# CY8C4125AZI-S433.net
KiCad netlist of a schematic drawn in Altium Designer
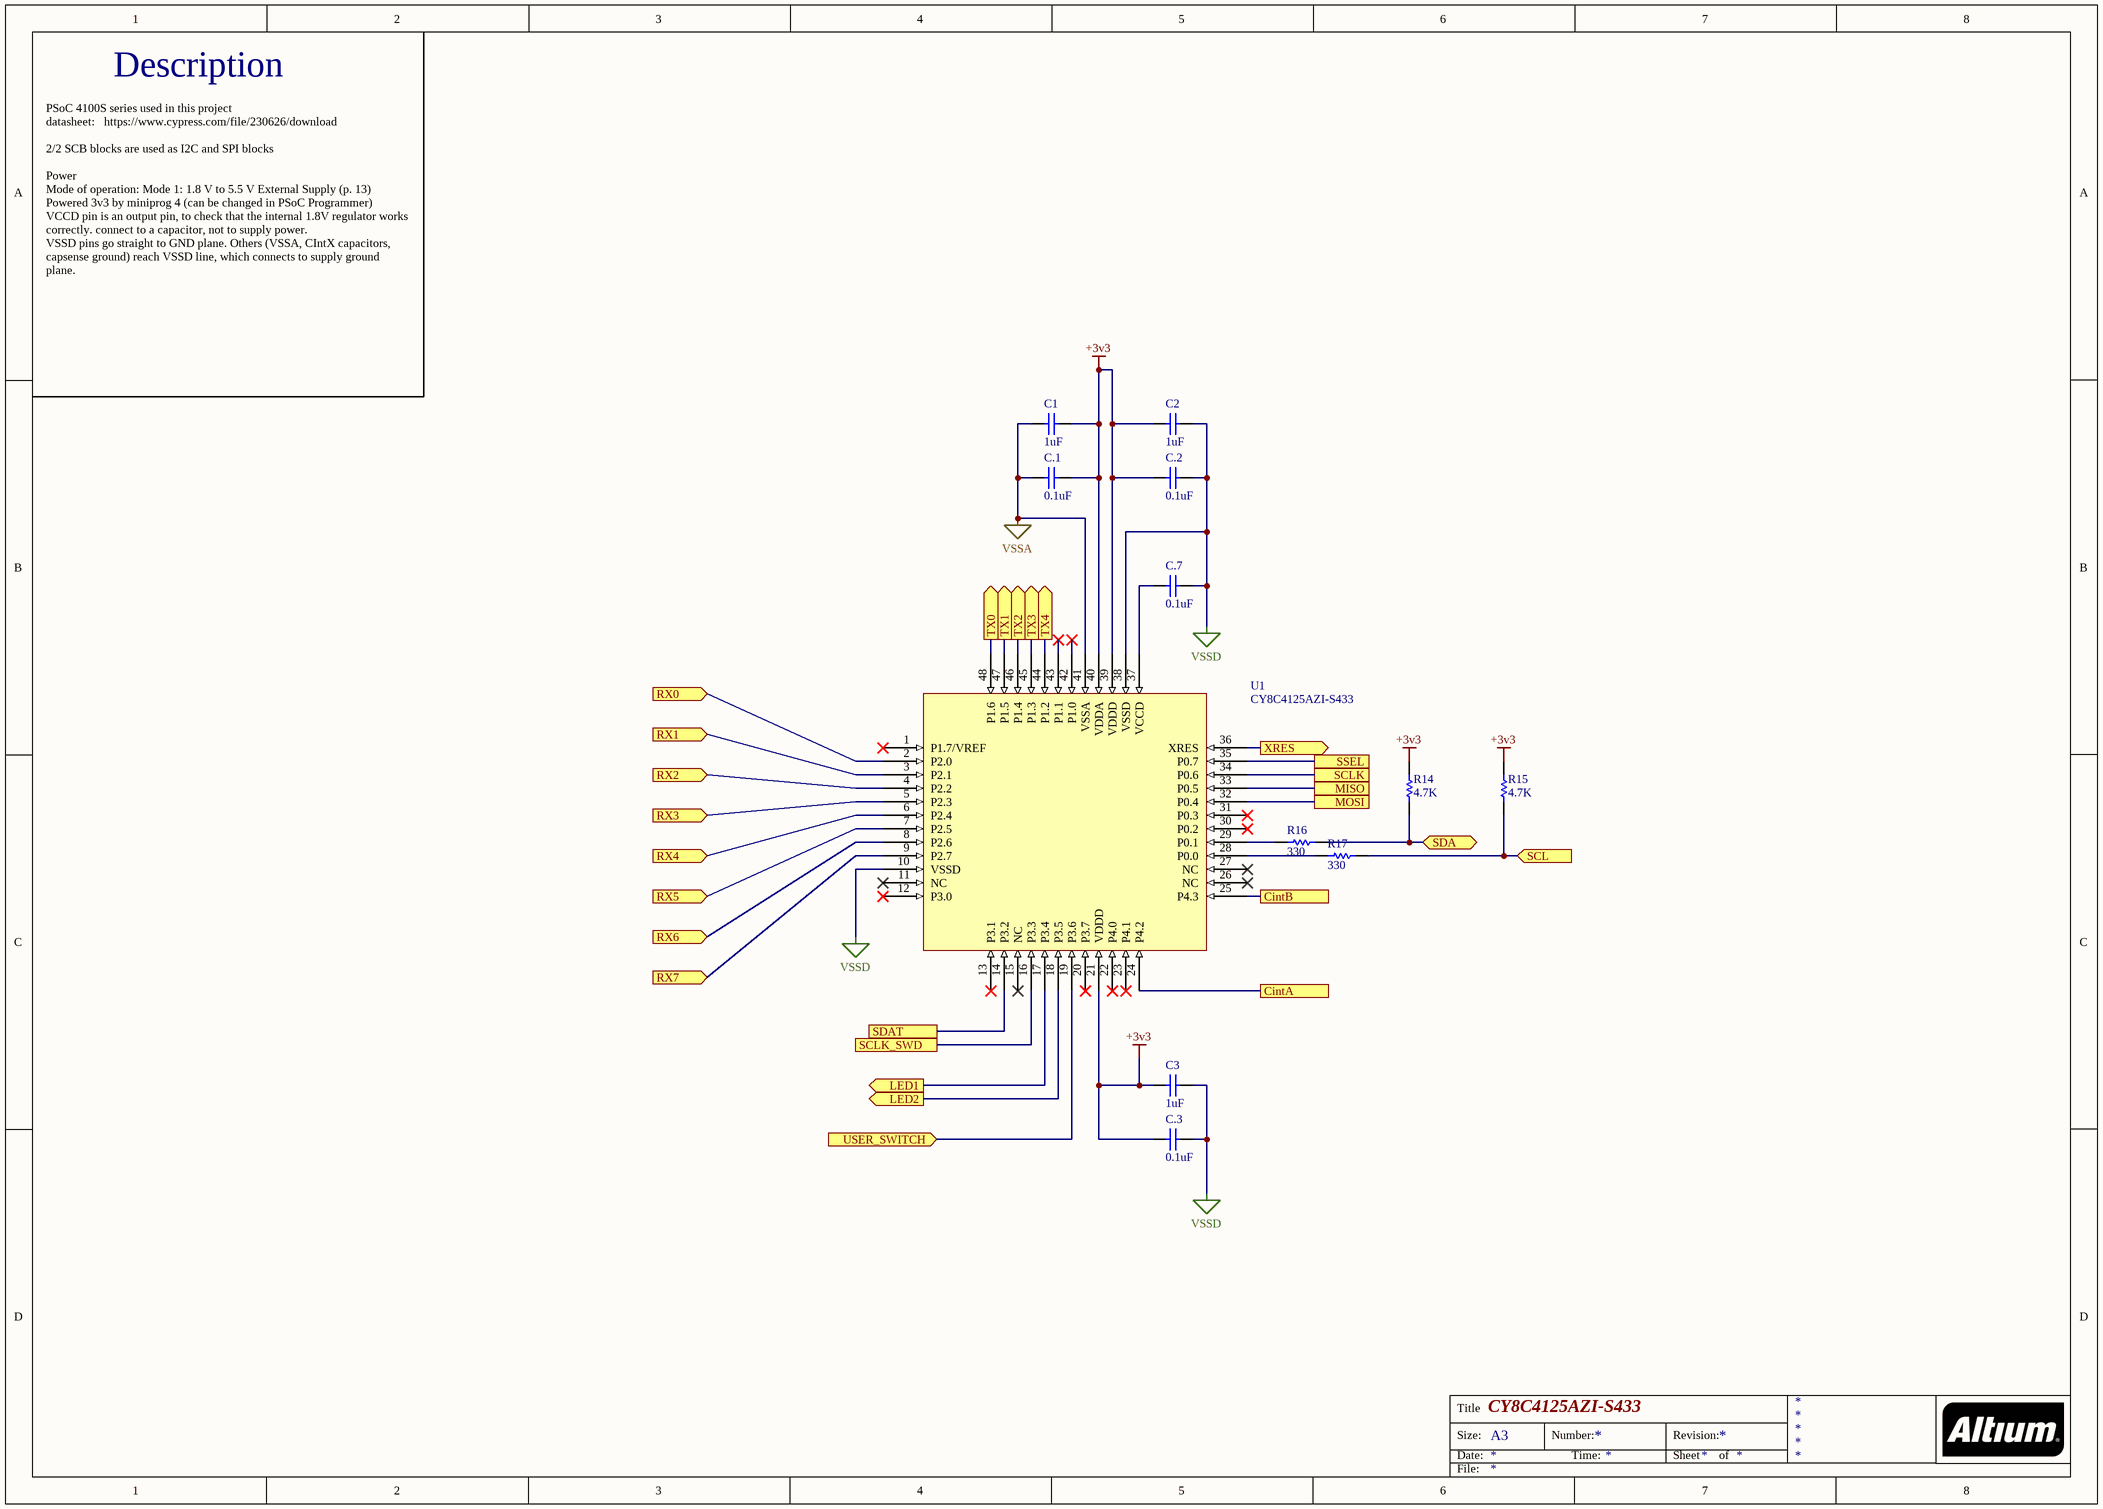
[diagram p0: CY8C4125AZI-S433.SchDoc]

(export (version "E")
  (design (tool "Eeschema 10.0.6"))
  (components
    (comp (ref "C.1")
      (value "0.1uF")
      (footprint "CAPC0603(1608)100_N")
      (description "CAP 0.1 uF 50V ±20% 0603 (1608 Metric) Thickness 1mm SMD")
      (fields (field (name "TOLERANCE") "Â±20%"))
      (libsource (lib "Altium Content Vault") (part "CAP"))
    )
    (comp (ref "C.2")
      (value "0.1uF")
      (footprint "CAPC0603(1608)100_N")
      (description "CAP 0.1 uF 50V ±20% 0603 (1608 Metric) Thickness 1mm SMD")
      (fields (field (name "TOLERANCE") "Â±20%"))
      (libsource (lib "Altium Content Vault") (part "CAP"))
    )
    (comp (ref "C.3")
      (value "0.1uF")
      (footprint "CAPC0603(1608)100_N")
      (description "CAP 0.1 uF 50V ±20% 0603 (1608 Metric) Thickness 1mm SMD")
      (fields (field (name "TOLERANCE") "Â±20%"))
      (libsource (lib "Altium Content Vault") (part "CAP"))
    )
    (comp (ref "C.7")
      (value "0.1uF")
      (footprint "CAPC0603(1608)100_N")
      (description "CAP 0.1 uF 50V ±20% 0603 (1608 Metric) Thickness 1mm SMD")
      (fields (field (name "TOLERANCE") "Â±20%"))
      (libsource (lib "Altium Content Vault") (part "CAP"))
    )
    (comp (ref "C1")
      (value "1uF")
      (footprint "CAPC0603(1608)100_N")
      (description "CAP 1uF 50V ±20% 0603 (1608 Metric) Thickness 1mm SMD")
      (fields (field (name "TOLERANCE") "Â±20%"))
      (libsource (lib "Altium Content Vault") (part "CAP"))
    )
    (comp (ref "C2")
      (value "1uF")
      (footprint "CAPC0603(1608)100_N")
      (description "CAP 1uF 50V ±20% 0603 (1608 Metric) Thickness 1mm SMD")
      (fields (field (name "TOLERANCE") "Â±20%"))
      (libsource (lib "Altium Content Vault") (part "CAP"))
    )
    (comp (ref "C3")
      (value "1uF")
      (footprint "CAPC0603(1608)100_N")
      (description "CAP 1uF 50V ±20% 0603 (1608 Metric) Thickness 1mm SMD")
      (fields (field (name "TOLERANCE") "Â±20%"))
      (libsource (lib "Altium Content Vault") (part "CAP"))
    )
    (comp (ref "R14")
      (value "4.7K")
      (footprint "RESC1608X55X25ML10T15")
      (fields (field (name "TOLERANCE") "5%") (field (name "MANUFACTURER") "Yageo"))
      (libsource (lib "Altium Content Vault") (part "RES-2"))
    )
    (comp (ref "R15")
      (value "4.7K")
      (footprint "RESC1608X55X25ML10T15")
      (fields (field (name "TOLERANCE") "5%") (field (name "MANUFACTURER") "Yageo"))
      (libsource (lib "Altium Content Vault") (part "RES-2"))
    )
    (comp (ref "R16")
      (value "330")
      (footprint "RESC0603(1608)_L")
      (description "330R 0.1W 5% 0603 (1608 Metric)  SMD")
      (fields (field (name "TOLERANCE") "5 %") (field (name "POWER") "0.1 W"))
      (libsource (lib "Altium Content Vault") (part "RES"))
    )
    (comp (ref "R17")
      (value "330")
      (footprint "RESC0603(1608)_L")
      (description "330R 0.1W 5% 0603 (1608 Metric)  SMD")
      (fields (field (name "TOLERANCE") "5 %") (field (name "POWER") "0.1 W"))
      (libsource (lib "Altium Content Vault") (part "RES"))
    )
    (comp (ref "U1")
      (value "CY8C4125AZI-S433")
      (footprint "CY8C4125AZI-S433")
      (libsource (lib "PSOC") (part "CY8C4125AZI-S433"))
    )
  )
  (nets
    (net (code "1") (name "+3v3") (class "Default")
      (node (ref "C.1") (pin "2") (pinfunction "2_2") (pintype "passive"))
      (node (ref "C.2") (pin "1") (pinfunction "1_1") (pintype "passive"))
      (node (ref "C.3") (pin "1") (pinfunction "1_1") (pintype "passive"))
      (node (ref "C1") (pin "2") (pinfunction "2_2") (pintype "passive"))
      (node (ref "C2") (pin "1") (pinfunction "1_1") (pintype "passive"))
      (node (ref "C3") (pin "1") (pinfunction "1_1") (pintype "passive"))
      (node (ref "R14") (pin "2") (pinfunction "2_2") (pintype "passive"))
      (node (ref "R15") (pin "2") (pinfunction "2_2") (pintype "passive"))
      (node (ref "U1") (pin "21") (pinfunction "VDDD_21") (pintype "input"))
      (node (ref "U1") (pin "39") (pinfunction "VDDD_39") (pintype "input"))
      (node (ref "U1") (pin "40") (pinfunction "VDDA_40") (pintype "input"))
    )
    (net (code "2") (name "/CintA") (class "Default")
      (node (ref "U1") (pin "24") (pinfunction "P4.2_24") (pintype "input"))
    )
    (net (code "3") (name "/CintB") (class "Default")
      (node (ref "U1") (pin "25") (pinfunction "P4.3_25") (pintype "input"))
    )
    (net (code "4") (name "/LED1") (class "Default")
      (node (ref "U1") (pin "17") (pinfunction "P3.4_17") (pintype "input"))
    )
    (net (code "5") (name "/LED2") (class "Default")
      (node (ref "U1") (pin "18") (pinfunction "P3.5_18") (pintype "input"))
    )
    (net (code "6") (name "/MISO") (class "Default")
      (node (ref "U1") (pin "33") (pinfunction "P0.5_33") (pintype "input"))
    )
    (net (code "7") (name "/MOSI") (class "Default")
      (node (ref "U1") (pin "32") (pinfunction "P0.4_32") (pintype "input"))
    )
    (net (code "8") (name "/RX0") (class "Default")
      (node (ref "U1") (pin "2") (pinfunction "P2.0_2") (pintype "input"))
    )
    (net (code "9") (name "/RX1") (class "Default")
      (node (ref "U1") (pin "3") (pinfunction "P2.1_3") (pintype "input"))
    )
    (net (code "10") (name "/RX2") (class "Default")
      (node (ref "U1") (pin "4") (pinfunction "P2.2_4") (pintype "input"))
    )
    (net (code "11") (name "/RX3") (class "Default")
      (node (ref "U1") (pin "5") (pinfunction "P2.3_5") (pintype "input"))
    )
    (net (code "12") (name "/RX4") (class "Default")
      (node (ref "U1") (pin "6") (pinfunction "P2.4_6") (pintype "input"))
    )
    (net (code "13") (name "/RX5") (class "Default")
      (node (ref "U1") (pin "7") (pinfunction "P2.5_7") (pintype "input"))
    )
    (net (code "14") (name "/RX6") (class "Default")
      (node (ref "U1") (pin "8") (pinfunction "P2.6_8") (pintype "input"))
    )
    (net (code "15") (name "/RX7") (class "Default")
      (node (ref "U1") (pin "9") (pinfunction "P2.7_9") (pintype "input"))
    )
    (net (code "16") (name "/SCL") (class "Default")
      (node (ref "R15") (pin "1") (pinfunction "1_1") (pintype "passive"))
      (node (ref "R17") (pin "2") (pinfunction "2_2") (pintype "passive"))
    )
    (net (code "17") (name "/SCLK") (class "Default")
      (node (ref "U1") (pin "34") (pinfunction "P0.6_34") (pintype "input"))
    )
    (net (code "18") (name "/SCLK_SWD") (class "Default")
      (node (ref "U1") (pin "16") (pinfunction "P3.3_16") (pintype "input"))
    )
    (net (code "19") (name "/SDA") (class "Default")
      (node (ref "R14") (pin "1") (pinfunction "1_1") (pintype "passive"))
      (node (ref "R16") (pin "2") (pinfunction "2_2") (pintype "passive"))
    )
    (net (code "20") (name "/SDAT") (class "Default")
      (node (ref "U1") (pin "14") (pinfunction "P3.2_14") (pintype "input"))
    )
    (net (code "21") (name "/SSEL") (class "Default")
      (node (ref "U1") (pin "35") (pinfunction "P0.7_35") (pintype "input"))
    )
    (net (code "22") (name "/TX0") (class "Default")
      (node (ref "U1") (pin "48") (pinfunction "P1.6_48") (pintype "input"))
    )
    (net (code "23") (name "/TX1") (class "Default")
      (node (ref "U1") (pin "47") (pinfunction "P1.5_47") (pintype "input"))
    )
    (net (code "24") (name "/TX2") (class "Default")
      (node (ref "U1") (pin "46") (pinfunction "P1.4_46") (pintype "input"))
    )
    (net (code "25") (name "/TX3") (class "Default")
      (node (ref "U1") (pin "45") (pinfunction "P1.3_45") (pintype "input"))
    )
    (net (code "26") (name "/TX4") (class "Default")
      (node (ref "U1") (pin "44") (pinfunction "P1.2_44") (pintype "input"))
    )
    (net (code "27") (name "/USER_SWITCH") (class "Default")
      (node (ref "U1") (pin "19") (pinfunction "P3.6_19") (pintype "input"))
    )
    (net (code "28") (name "/XRES") (class "Default")
      (node (ref "U1") (pin "36") (pinfunction "XRES_36") (pintype "input"))
    )
    (net (code "29") (name "Net-(U1-P0.0)") (class "Default")
      (node (ref "R17") (pin "1") (pinfunction "1_1") (pintype "passive"))
      (node (ref "U1") (pin "28") (pinfunction "P0.0_28") (pintype "input"))
    )
    (net (code "30") (name "Net-(U1-P0.1)") (class "Default")
      (node (ref "R16") (pin "1") (pinfunction "1_1") (pintype "passive"))
      (node (ref "U1") (pin "29") (pinfunction "P0.1_29") (pintype "input"))
    )
    (net (code "31") (name "Net-(U1-VCCD)") (class "Default")
      (node (ref "C.7") (pin "1") (pinfunction "1_1") (pintype "passive"))
      (node (ref "U1") (pin "37") (pinfunction "VCCD_37") (pintype "input"))
    )
    (net (code "32") (name "VSSA") (class "Default")
      (node (ref "C.1") (pin "1") (pinfunction "1_1") (pintype "passive"))
      (node (ref "C1") (pin "1") (pinfunction "1_1") (pintype "passive"))
      (node (ref "U1") (pin "41") (pinfunction "VSSA_41") (pintype "input"))
    )
    (net (code "33") (name "VSSD") (class "Default")
      (node (ref "C.2") (pin "2") (pinfunction "2_2") (pintype "passive"))
      (node (ref "C.3") (pin "2") (pinfunction "2_2") (pintype "passive"))
      (node (ref "C.7") (pin "2") (pinfunction "2_2") (pintype "passive"))
      (node (ref "C2") (pin "2") (pinfunction "2_2") (pintype "passive"))
      (node (ref "C3") (pin "2") (pinfunction "2_2") (pintype "passive"))
      (node (ref "U1") (pin "10") (pinfunction "VSSD_10") (pintype "input"))
      (node (ref "U1") (pin "38") (pinfunction "VSSD_38") (pintype "input"))
    )
    (net (code "34") (name "unconnected-(U1-NC-Pad11)") (class "Default")
      (node (ref "U1") (pin "11") (pinfunction "NC_11") (pintype "input+no_connect"))
    )
    (net (code "35") (name "unconnected-(U1-NC-Pad15)") (class "Default")
      (node (ref "U1") (pin "15") (pinfunction "NC_15") (pintype "input+no_connect"))
    )
    (net (code "36") (name "unconnected-(U1-NC-Pad26)") (class "Default")
      (node (ref "U1") (pin "26") (pinfunction "NC_26") (pintype "input+no_connect"))
    )
    (net (code "37") (name "unconnected-(U1-NC-Pad27)") (class "Default")
      (node (ref "U1") (pin "27") (pinfunction "NC_27") (pintype "input+no_connect"))
    )
    (net (code "38") (name "unconnected-(U1-P0.2-Pad30)") (class "Default")
      (node (ref "U1") (pin "30") (pinfunction "P0.2_30") (pintype "input+no_connect"))
    )
    (net (code "39") (name "unconnected-(U1-P0.3-Pad31)") (class "Default")
      (node (ref "U1") (pin "31") (pinfunction "P0.3_31") (pintype "input+no_connect"))
    )
    (net (code "40") (name "unconnected-(U1-P1.0-Pad42)") (class "Default")
      (node (ref "U1") (pin "42") (pinfunction "P1.0_42") (pintype "input+no_connect"))
    )
    (net (code "41") (name "unconnected-(U1-P1.1-Pad43)") (class "Default")
      (node (ref "U1") (pin "43") (pinfunction "P1.1_43") (pintype "input+no_connect"))
    )
    (net (code "42") (name "unconnected-(U1-P1.7{slash}VREF-Pad1)") (class "Default")
      (node (ref "U1") (pin "1") (pinfunction "P1.7/VREF_1") (pintype "input+no_connect"))
    )
    (net (code "43") (name "unconnected-(U1-P3.0-Pad12)") (class "Default")
      (node (ref "U1") (pin "12") (pinfunction "P3.0_12") (pintype "input+no_connect"))
    )
    (net (code "44") (name "unconnected-(U1-P3.1-Pad13)") (class "Default")
      (node (ref "U1") (pin "13") (pinfunction "P3.1_13") (pintype "input+no_connect"))
    )
    (net (code "45") (name "unconnected-(U1-P3.7-Pad20)") (class "Default")
      (node (ref "U1") (pin "20") (pinfunction "P3.7_20") (pintype "input+no_connect"))
    )
    (net (code "46") (name "unconnected-(U1-P4.0-Pad22)") (class "Default")
      (node (ref "U1") (pin "22") (pinfunction "P4.0_22") (pintype "input+no_connect"))
    )
    (net (code "47") (name "unconnected-(U1-P4.1-Pad23)") (class "Default")
      (node (ref "U1") (pin "23") (pinfunction "P4.1_23") (pintype "input+no_connect"))
    )
  )
)
